# Power.net
KiCad netlist of a schematic drawn in Altium Designer
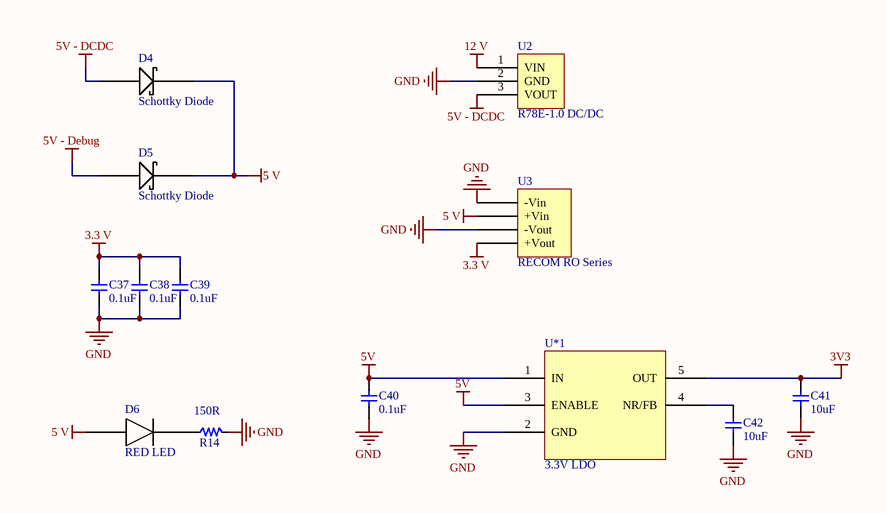
[diagram p0: Power.SchDoc]

(export (version "E")
  (design (tool "Eeschema 10.0.6"))
  (components
    (comp (ref "C37")
      (value "0.1uF")
      (footprint "PCB_GENERIC_SMD_0603")
      (description "CAP CER 0603 0.1uF 16V X5R 20%")
      (fields (field (name "TOLERANCE") "20%") (field (name "VOLTAGE") "16V"))
      (libsource (lib "CAP-0603 (2)") (part "C060-000U1-00"))
    )
    (comp (ref "C38")
      (value "0.1uF")
      (footprint "PCB_GENERIC_SMD_0603")
      (description "CAP CER 0603 0.1uF 16V X5R 20%")
      (fields (field (name "TOLERANCE") "20%") (field (name "VOLTAGE") "16V"))
      (libsource (lib "CAP-0603 (2)") (part "C060-000U1-00"))
    )
    (comp (ref "C39")
      (value "0.1uF")
      (footprint "PCB_GENERIC_SMD_0603")
      (description "CAP CER 0603 0.1uF 16V X5R 20%")
      (fields (field (name "TOLERANCE") "20%") (field (name "VOLTAGE") "16V"))
      (libsource (lib "CAP-0603 (2)") (part "C060-000U1-00"))
    )
    (comp (ref "C40")
      (value "0.1uF")
      (footprint "PCB_GENERIC_SMD_0603")
      (description "CAP CER 0603 0.1uF 16V X5R 20%")
      (fields (field (name "TOLERANCE") "20%") (field (name "VOLTAGE") "16V"))
      (libsource (lib "CAP-0603 (2)") (part "C060-000U1-00"))
    )
    (comp (ref "C41")
      (value "10uF")
      (footprint "PCB_GENERIC_SMD_0603")
      (description "CAP CER 0603 10uF 6.3V X5R 20%")
      (fields (field (name "TOLERANCE") "20%") (field (name "VOLTAGE") "6.3V"))
      (libsource (lib "CAP-0603 (2)") (part "C060-0010U-00"))
    )
    (comp (ref "C42")
      (value "10uF")
      (footprint "PCB_GENERIC_SMD_0603")
      (description "CAP CER 0603 10uF 6.3V X5R 20%")
      (fields (field (name "TOLERANCE") "20%") (field (name "VOLTAGE") "6.3V"))
      (libsource (lib "CAP-0603 (2)") (part "C060-0010U-00"))
    )
    (comp (ref "D4")
      (value "Schottky Diode")
      (footprint "ON Semi Schottky Diode - MBRM110LT1G")
      (libsource (lib "ON Semi Schottky Diode") (part "ON Semi Schottky Diode - MBRM110LT1G"))
    )
    (comp (ref "D5")
      (value "Schottky Diode")
      (footprint "ON Semi Schottky Diode - MBRM110LT1G")
      (libsource (lib "ON Semi Schottky Diode") (part "ON Semi Schottky Diode - MBRM110LT1G"))
    )
    (comp (ref "D6")
      (value "RED LED")
      (footprint "SMD_0603_LED")
      (libsource (lib "0603 LED") (part "SMD_0603_LED"))
    )
    (comp (ref "R14")
      (value "SCH_GENERIC_RESISTOR_0603")
      (footprint "PCB_GENERIC_SMD_0603")
      (description "Generic SMD resistor 0603")
      (libsource (lib "SCH_GENERIC_RESISTOR_0603") (part "SCH_GENERIC_RESISTOR_0603"))
    )
    (comp (ref "U*1")
      (value "3.3V LDO")
      (footprint "SOT95P280X145-5N")
      (description "Linear Voltage Regulator IC Positive Fixed 1 Output 3.3V 400mA SOT-23-5")
      (libsource (lib "3V3LDO_TPS73633DBVR_SOT23-5") (part "3V3LDO_TPS73633DBVR_SOT23-5"))
    )
    (comp (ref "U2")
      (value "R78E-1.0 DC/DC")
      (footprint "R78-1.0")
      (libsource (lib "Recom R78E-1.0") (part "R78E-1.0"))
    )
    (comp (ref "U3")
      (value "RECOM RO Series")
      (footprint "RECOM RO Series 1W DCDC")
      (libsource (lib "RECOM RO Series 1W DCDC") (part "RECOM RO Series DCDC Converter"))
    )
  )
  (nets
    (net (code "1") (name "3.3 V") (class "Default")
      (node (ref "C37") (pin "2") (pinfunction "2_2") (pintype "passive"))
      (node (ref "C38") (pin "2") (pinfunction "2_2") (pintype "passive"))
      (node (ref "C39") (pin "2") (pinfunction "2_2") (pintype "passive"))
      (node (ref "U3") (pin "4") (pinfunction "+Vout_4") (pintype "passive"))
    )
    (net (code "2") (name "3V3") (class "Default")
      (node (ref "C41") (pin "2") (pinfunction "2_2") (pintype "passive"))
      (node (ref "U*1") (pin "5") (pinfunction "OUT_5") (pintype "power_in"))
    )
    (net (code "3") (name "5 V") (class "Default")
      (node (ref "D4") (pin "1") (pinfunction "1_1") (pintype "passive"))
      (node (ref "D5") (pin "1") (pinfunction "1_1") (pintype "passive"))
      (node (ref "D6") (pin "1") (pinfunction "1_1") (pintype "passive"))
      (node (ref "U3") (pin "2") (pinfunction "+Vin_2") (pintype "passive"))
    )
    (net (code "4") (name "5V") (class "Default")
      (node (ref "C40") (pin "2") (pinfunction "2_2") (pintype "passive"))
      (node (ref "U*1") (pin "1") (pinfunction "IN_1") (pintype "power_in"))
      (node (ref "U*1") (pin "3") (pinfunction "ENABLE_3") (pintype "power_in"))
    )
    (net (code "5") (name "5V - DCDC") (class "Default")
      (node (ref "D4") (pin "2") (pinfunction "2_2") (pintype "passive"))
      (node (ref "U2") (pin "3") (pinfunction "VOUT_3") (pintype "passive"))
    )
    (net (code "6") (name "5V - Debug") (class "Default")
      (node (ref "D5") (pin "2") (pinfunction "2_2") (pintype "passive"))
    )
    (net (code "7") (name "12 V") (class "Default")
      (node (ref "U2") (pin "1") (pinfunction "VIN_1") (pintype "passive"))
    )
    (net (code "8") (name "GND") (class "Default")
      (node (ref "C37") (pin "1") (pinfunction "1_1") (pintype "passive"))
      (node (ref "C38") (pin "1") (pinfunction "1_1") (pintype "passive"))
      (node (ref "C39") (pin "1") (pinfunction "1_1") (pintype "passive"))
      (node (ref "C40") (pin "1") (pinfunction "1_1") (pintype "passive"))
      (node (ref "C41") (pin "1") (pinfunction "1_1") (pintype "passive"))
      (node (ref "C42") (pin "1") (pinfunction "1_1") (pintype "passive"))
      (node (ref "R14") (pin "2") (pinfunction "2_2") (pintype "passive"))
      (node (ref "U*1") (pin "2") (pinfunction "GND_2") (pintype "power_in"))
      (node (ref "U2") (pin "2") (pinfunction "GND_2") (pintype "passive"))
      (node (ref "U3") (pin "1") (pinfunction "-Vin_1") (pintype "passive"))
      (node (ref "U3") (pin "3") (pinfunction "-Vout_3") (pintype "passive"))
    )
    (net (code "9") (name "Net-(D6-Pad2)") (class "Default")
      (node (ref "D6") (pin "2") (pinfunction "2_2") (pintype "passive"))
      (node (ref "R14") (pin "1") (pinfunction "1_1") (pintype "passive"))
    )
    (net (code "10") (name "Net-(U*1-NR{slash}FB)") (class "Default")
      (node (ref "C42") (pin "2") (pinfunction "2_2") (pintype "passive"))
      (node (ref "U*1") (pin "4") (pinfunction "NR/FB_4") (pintype "power_in"))
    )
  )
)
